# v002.net
KiCad netlist of a schematic drawn in EAGLE
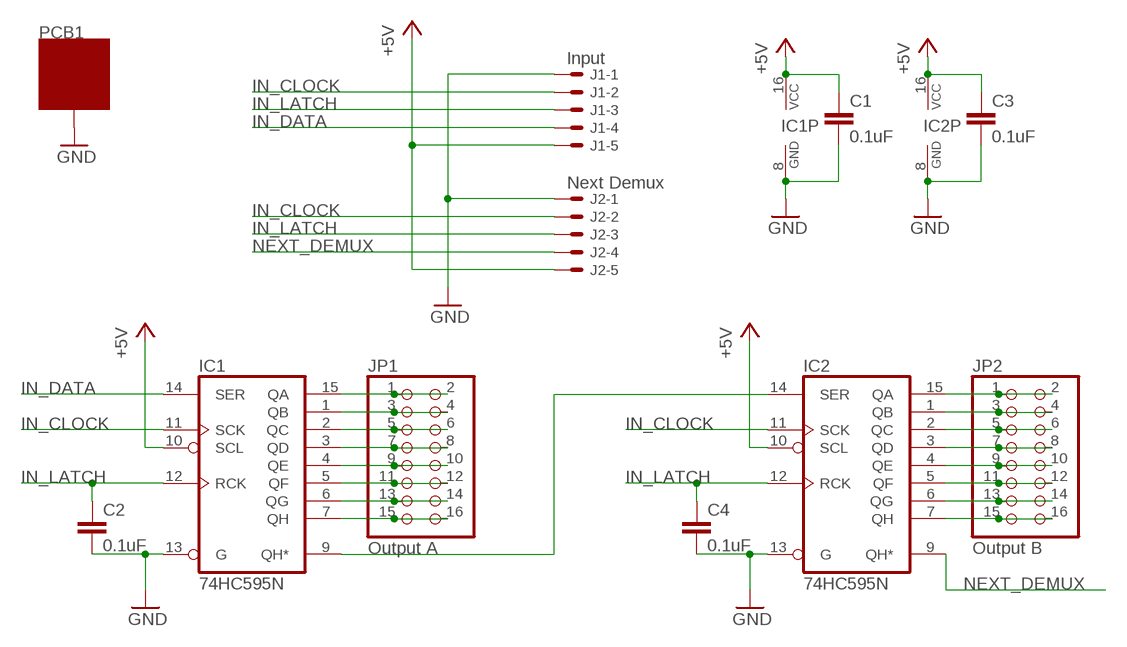
[diagram p0: schematic, sheet 1]

(export (version "E")
  (design (tool "Eeschema 10.0.6"))
  (components
    (comp (ref "C1")
      (value "0.1uF")
      (footprint "eagle-import:C050-024X044")
      (libsource (lib "eagle-import") (part "C-EU050-024X044"))
    )
    (comp (ref "C2")
      (value "0.1uF")
      (footprint "eagle-import:C050-024X044")
      (libsource (lib "eagle-import") (part "C-EU050-024X044"))
    )
    (comp (ref "C3")
      (value "0.1uF")
      (footprint "eagle-import:C050-024X044")
      (libsource (lib "eagle-import") (part "C-EU050-024X044"))
    )
    (comp (ref "C4")
      (value "0.1uF")
      (footprint "eagle-import:C050-024X044")
      (libsource (lib "eagle-import") (part "C-EU050-024X044"))
    )
    (comp (ref "IC1")
      (value "74HC595N")
      (footprint "eagle-import:DIL16")
      (libsource (lib "eagle-import") (part "74595NHC"))
    )
    (comp (ref "IC2")
      (value "74HC595N")
      (footprint "eagle-import:DIL16")
      (libsource (lib "eagle-import") (part "74595NHC"))
    )
    (comp (ref "J1")
      (value "Input")
      (footprint "eagle-import:6410-05")
      (libsource (lib "eagle-import") (part "22-?-0527-2051"))
    )
    (comp (ref "J2")
      (value "Next Demux")
      (footprint "eagle-import:6410-05")
      (libsource (lib "eagle-import") (part "22-?-0527-2051"))
    )
    (comp (ref "JP1")
      (value "Output A")
      (footprint "eagle-import:2X08")
      (libsource (lib "eagle-import") (part "PINHD-2X8"))
    )
    (comp (ref "JP2")
      (value "Output B")
      (footprint "eagle-import:2X08")
      (libsource (lib "eagle-import") (part "PINHD-2X8"))
    )
    (comp (ref "PCB1")
      (value "ZZZ_MODULE05X05")
      (footprint "eagle-import:ZZZ_MODULE_05X05")
      (libsource (lib "eagle-import") (part "ZZZ_MODULE05X05"))
    )
  )
  (nets
    (net (code "1") (name "+5V") (class "Default")
      (node (ref "C1") (pin "1") (pinfunction "1_1") (pintype "passive"))
      (node (ref "C3") (pin "1") (pinfunction "1_1") (pintype "passive"))
      (node (ref "IC1") (pin "10") (pinfunction "SCL_10") (pintype "input"))
      (node (ref "IC1") (pin "16") (pinfunction "VCC_16") (pintype "power_in"))
      (node (ref "IC2") (pin "10") (pinfunction "SCL_10") (pintype "input"))
      (node (ref "IC2") (pin "16") (pinfunction "VCC_16") (pintype "power_in"))
      (node (ref "J1") (pin "5") (pinfunction "S_5") (pintype "passive"))
      (node (ref "J2") (pin "5") (pinfunction "S_5") (pintype "passive"))
    )
    (net (code "2") (name "/IN_CLOCK") (class "Default")
      (node (ref "IC1") (pin "11") (pinfunction "SCK_11") (pintype "input"))
      (node (ref "IC2") (pin "11") (pinfunction "SCK_11") (pintype "input"))
      (node (ref "J1") (pin "2") (pinfunction "S_2") (pintype "passive"))
      (node (ref "J2") (pin "2") (pinfunction "S_2") (pintype "passive"))
    )
    (net (code "3") (name "/IN_DATA") (class "Default")
      (node (ref "IC1") (pin "14") (pinfunction "SER_14") (pintype "input"))
      (node (ref "J1") (pin "4") (pinfunction "S_4") (pintype "passive"))
    )
    (net (code "4") (name "/IN_LATCH") (class "Default")
      (node (ref "C2") (pin "1") (pinfunction "1_1") (pintype "passive"))
      (node (ref "C4") (pin "1") (pinfunction "1_1") (pintype "passive"))
      (node (ref "IC1") (pin "12") (pinfunction "RCK_12") (pintype "input"))
      (node (ref "IC2") (pin "12") (pinfunction "RCK_12") (pintype "input"))
      (node (ref "J1") (pin "3") (pinfunction "S_3") (pintype "passive"))
      (node (ref "J2") (pin "3") (pinfunction "S_3") (pintype "passive"))
    )
    (net (code "5") (name "/NEXT_DEMUX") (class "Default")
      (node (ref "IC2") (pin "9") (pinfunction "QH*_9") (pintype "tri_state"))
      (node (ref "J2") (pin "4") (pinfunction "S_4") (pintype "passive"))
    )
    (net (code "6") (name "GND") (class "Default")
      (node (ref "C1") (pin "2") (pinfunction "2_2") (pintype "passive"))
      (node (ref "C2") (pin "2") (pinfunction "2_2") (pintype "passive"))
      (node (ref "C3") (pin "2") (pinfunction "2_2") (pintype "passive"))
      (node (ref "C4") (pin "2") (pinfunction "2_2") (pintype "passive"))
      (node (ref "IC1") (pin "13") (pinfunction "G_13") (pintype "input"))
      (node (ref "IC1") (pin "8") (pinfunction "GND_8") (pintype "power_in"))
      (node (ref "IC2") (pin "13") (pinfunction "G_13") (pintype "input"))
      (node (ref "IC2") (pin "8") (pinfunction "GND_8") (pintype "power_in"))
      (node (ref "J1") (pin "1") (pinfunction "S_1") (pintype "passive"))
      (node (ref "J2") (pin "1") (pinfunction "S_1") (pintype "passive"))
      (node (ref "PCB1") (pin "GND@1") (pinfunction "GND_GND@1") (pintype "power_in"))
      (node (ref "PCB1") (pin "GND@2") (pinfunction "GND_GND@2") (pintype "power_in"))
      (node (ref "PCB1") (pin "GND@3") (pinfunction "GND_GND@3") (pintype "power_in"))
      (node (ref "PCB1") (pin "GND@4") (pinfunction "GND_GND@4") (pintype "power_in"))
      (node (ref "PCB1") (pin "GND@5") (pinfunction "GND_GND@5") (pintype "power_in"))
      (node (ref "PCB1") (pin "GND@6") (pinfunction "GND_GND@6") (pintype "power_in"))
      (node (ref "PCB1") (pin "GND@7") (pinfunction "GND_GND@7") (pintype "power_in"))
      (node (ref "PCB1") (pin "GND@8") (pinfunction "GND_GND@8") (pintype "power_in"))
    )
    (net (code "7") (name "Net-(IC1A-QA)") (class "Default")
      (node (ref "IC1") (pin "15") (pinfunction "QA_15") (pintype "tri_state"))
      (node (ref "JP1") (pin "1") (pinfunction "1_1") (pintype "passive"))
      (node (ref "JP1") (pin "2") (pinfunction "2_2") (pintype "passive"))
    )
    (net (code "8") (name "Net-(IC1A-QB)") (class "Default")
      (node (ref "IC1") (pin "1") (pinfunction "QB_1") (pintype "tri_state"))
      (node (ref "JP1") (pin "3") (pinfunction "3_3") (pintype "passive"))
      (node (ref "JP1") (pin "4") (pinfunction "4_4") (pintype "passive"))
    )
    (net (code "9") (name "Net-(IC1A-QC)") (class "Default")
      (node (ref "IC1") (pin "2") (pinfunction "QC_2") (pintype "tri_state"))
      (node (ref "JP1") (pin "5") (pinfunction "5_5") (pintype "passive"))
      (node (ref "JP1") (pin "6") (pinfunction "6_6") (pintype "passive"))
    )
    (net (code "10") (name "Net-(IC1A-QD)") (class "Default")
      (node (ref "IC1") (pin "3") (pinfunction "QD_3") (pintype "tri_state"))
      (node (ref "JP1") (pin "7") (pinfunction "7_7") (pintype "passive"))
      (node (ref "JP1") (pin "8") (pinfunction "8_8") (pintype "passive"))
    )
    (net (code "11") (name "Net-(IC1A-QE)") (class "Default")
      (node (ref "IC1") (pin "4") (pinfunction "QE_4") (pintype "tri_state"))
      (node (ref "JP1") (pin "10") (pinfunction "10_10") (pintype "passive"))
      (node (ref "JP1") (pin "9") (pinfunction "9_9") (pintype "passive"))
    )
    (net (code "12") (name "Net-(IC1A-QF)") (class "Default")
      (node (ref "IC1") (pin "5") (pinfunction "QF_5") (pintype "tri_state"))
      (node (ref "JP1") (pin "11") (pinfunction "11_11") (pintype "passive"))
      (node (ref "JP1") (pin "12") (pinfunction "12_12") (pintype "passive"))
    )
    (net (code "13") (name "Net-(IC1A-QG)") (class "Default")
      (node (ref "IC1") (pin "6") (pinfunction "QG_6") (pintype "tri_state"))
      (node (ref "JP1") (pin "13") (pinfunction "13_13") (pintype "passive"))
      (node (ref "JP1") (pin "14") (pinfunction "14_14") (pintype "passive"))
    )
    (net (code "14") (name "Net-(IC1A-QH)") (class "Default")
      (node (ref "IC1") (pin "7") (pinfunction "QH_7") (pintype "tri_state"))
      (node (ref "JP1") (pin "15") (pinfunction "15_15") (pintype "passive"))
      (node (ref "JP1") (pin "16") (pinfunction "16_16") (pintype "passive"))
    )
    (net (code "15") (name "Net-(IC1A-QH*)") (class "Default")
      (node (ref "IC1") (pin "9") (pinfunction "QH*_9") (pintype "tri_state"))
      (node (ref "IC2") (pin "14") (pinfunction "SER_14") (pintype "input"))
    )
    (net (code "16") (name "Net-(IC2A-QA)") (class "Default")
      (node (ref "IC2") (pin "15") (pinfunction "QA_15") (pintype "tri_state"))
      (node (ref "JP2") (pin "1") (pinfunction "1_1") (pintype "passive"))
      (node (ref "JP2") (pin "2") (pinfunction "2_2") (pintype "passive"))
    )
    (net (code "17") (name "Net-(IC2A-QB)") (class "Default")
      (node (ref "IC2") (pin "1") (pinfunction "QB_1") (pintype "tri_state"))
      (node (ref "JP2") (pin "3") (pinfunction "3_3") (pintype "passive"))
      (node (ref "JP2") (pin "4") (pinfunction "4_4") (pintype "passive"))
    )
    (net (code "18") (name "Net-(IC2A-QC)") (class "Default")
      (node (ref "IC2") (pin "2") (pinfunction "QC_2") (pintype "tri_state"))
      (node (ref "JP2") (pin "5") (pinfunction "5_5") (pintype "passive"))
      (node (ref "JP2") (pin "6") (pinfunction "6_6") (pintype "passive"))
    )
    (net (code "19") (name "Net-(IC2A-QD)") (class "Default")
      (node (ref "IC2") (pin "3") (pinfunction "QD_3") (pintype "tri_state"))
      (node (ref "JP2") (pin "7") (pinfunction "7_7") (pintype "passive"))
      (node (ref "JP2") (pin "8") (pinfunction "8_8") (pintype "passive"))
    )
    (net (code "20") (name "Net-(IC2A-QE)") (class "Default")
      (node (ref "IC2") (pin "4") (pinfunction "QE_4") (pintype "tri_state"))
      (node (ref "JP2") (pin "10") (pinfunction "10_10") (pintype "passive"))
      (node (ref "JP2") (pin "9") (pinfunction "9_9") (pintype "passive"))
    )
    (net (code "21") (name "Net-(IC2A-QF)") (class "Default")
      (node (ref "IC2") (pin "5") (pinfunction "QF_5") (pintype "tri_state"))
      (node (ref "JP2") (pin "11") (pinfunction "11_11") (pintype "passive"))
      (node (ref "JP2") (pin "12") (pinfunction "12_12") (pintype "passive"))
    )
    (net (code "22") (name "Net-(IC2A-QG)") (class "Default")
      (node (ref "IC2") (pin "6") (pinfunction "QG_6") (pintype "tri_state"))
      (node (ref "JP2") (pin "13") (pinfunction "13_13") (pintype "passive"))
      (node (ref "JP2") (pin "14") (pinfunction "14_14") (pintype "passive"))
    )
    (net (code "23") (name "Net-(IC2A-QH)") (class "Default")
      (node (ref "IC2") (pin "7") (pinfunction "QH_7") (pintype "tri_state"))
      (node (ref "JP2") (pin "15") (pinfunction "15_15") (pintype "passive"))
      (node (ref "JP2") (pin "16") (pinfunction "16_16") (pintype "passive"))
    )
  )
)
